# Whitespace_Daughtercard_spi_mux.net
KiCad netlist of a schematic drawn in Altium Designer
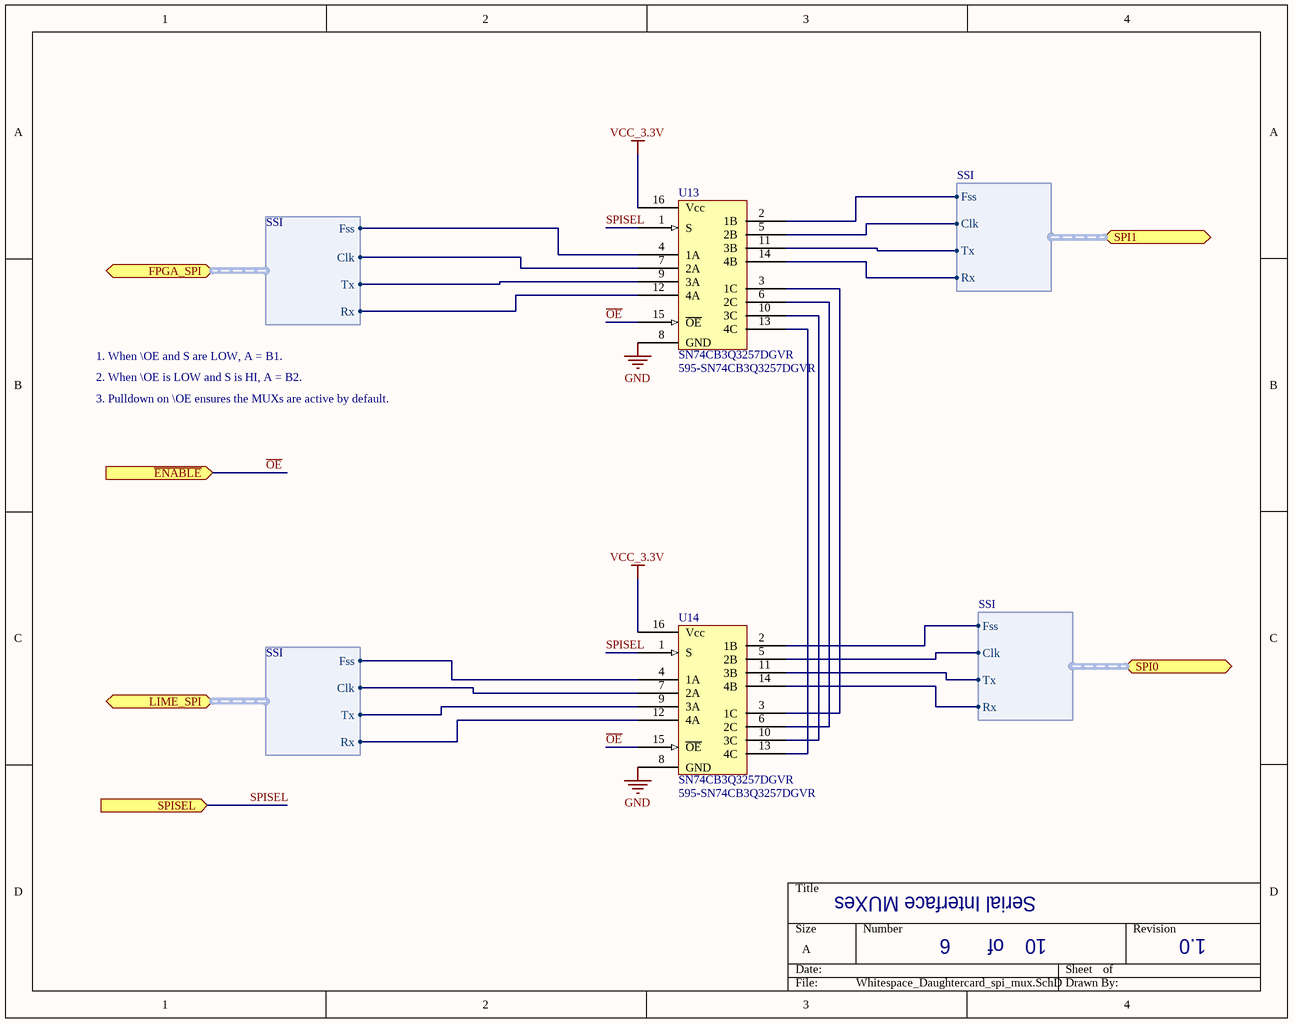
[diagram p0: Whitespace_Daughtercard_spi_mux.SchDoc]

(export (version "E")
  (design (tool "Eeschema 10.0.6"))
  (components
    (comp (ref "U13")
      (value "SN74CB3Q3257DGVR")
      (footprint "TVSOP16_v5")
      (description "4-bit MUX/DEMUX 1-of-2  0-5V SIG 3.3V CTRL TVSOP-16")
      (fields (field (name "SUPPLIER PART NUMBER 1") "595-SN74CB3Q3257DGVR"))
      (libsource (lib "RNG_Parts") (part "SN74CB3Q3257DGVR"))
    )
    (comp (ref "U14")
      (value "SN74CB3Q3257DGVR")
      (footprint "TVSOP16_v5")
      (description "4-bit MUX/DEMUX 1-of-2  0-5V SIG 3.3V CTRL TVSOP-16")
      (fields (field (name "SUPPLIER PART NUMBER 1") "595-SN74CB3Q3257DGVR"))
      (libsource (lib "RNG_Parts") (part "SN74CB3Q3257DGVR"))
    )
  )
  (nets
    (net (code "2") (name "/OE") (class "Default")
      (node (ref "U13") (pin "15") (pinfunction "OE_15") (pintype "input"))
      (node (ref "U14") (pin "15") (pinfunction "OE_15") (pintype "input"))
    )
    (net (code "3") (name "/SPISEL") (class "Default")
      (node (ref "U13") (pin "1") (pinfunction "S_1") (pintype "input"))
      (node (ref "U14") (pin "1") (pinfunction "S_1") (pintype "input"))
    )
    (net (code "5") (name "GND") (class "Default")
      (node (ref "U13") (pin "8") (pinfunction "GND_8") (pintype "power_in"))
      (node (ref "U14") (pin "8") (pinfunction "GND_8") (pintype "power_in"))
    )
    (net (code "6") (name "Net-(U13-1C)") (class "Default")
      (node (ref "U13") (pin "3") (pinfunction "1C_3") (pintype "passive"))
      (node (ref "U14") (pin "3") (pinfunction "1C_3") (pintype "passive"))
    )
    (net (code "7") (name "Net-(U13-2C)") (class "Default")
      (node (ref "U13") (pin "6") (pinfunction "2C_6") (pintype "passive"))
      (node (ref "U14") (pin "6") (pinfunction "2C_6") (pintype "passive"))
    )
    (net (code "8") (name "Net-(U13-3C)") (class "Default")
      (node (ref "U13") (pin "10") (pinfunction "3C_10") (pintype "passive"))
      (node (ref "U14") (pin "10") (pinfunction "3C_10") (pintype "passive"))
    )
    (net (code "9") (name "Net-(U13-4C)") (class "Default")
      (node (ref "U13") (pin "13") (pinfunction "4C_13") (pintype "passive"))
      (node (ref "U14") (pin "13") (pinfunction "4C_13") (pintype "passive"))
    )
    (net (code "10") (name "VCC_3.3V") (class "Default")
      (node (ref "U13") (pin "16") (pinfunction "Vcc_16") (pintype "power_in"))
      (node (ref "U14") (pin "16") (pinfunction "Vcc_16") (pintype "power_in"))
    )
    (net (code "11") (name "unconnected-(U13-1A-Pad4)") (class "Default")
      (node (ref "U13") (pin "4") (pinfunction "1A_4") (pintype "passive"))
    )
    (net (code "12") (name "unconnected-(U13-1B-Pad2)") (class "Default")
      (node (ref "U13") (pin "2") (pinfunction "1B_2") (pintype "passive"))
    )
    (net (code "13") (name "unconnected-(U13-2A-Pad7)") (class "Default")
      (node (ref "U13") (pin "7") (pinfunction "2A_7") (pintype "passive"))
    )
    (net (code "14") (name "unconnected-(U13-2B-Pad5)") (class "Default")
      (node (ref "U13") (pin "5") (pinfunction "2B_5") (pintype "passive"))
    )
    (net (code "15") (name "unconnected-(U13-3A-Pad9)") (class "Default")
      (node (ref "U13") (pin "9") (pinfunction "3A_9") (pintype "passive"))
    )
    (net (code "16") (name "unconnected-(U13-3B-Pad11)") (class "Default")
      (node (ref "U13") (pin "11") (pinfunction "3B_11") (pintype "passive"))
    )
    (net (code "17") (name "unconnected-(U13-4A-Pad12)") (class "Default")
      (node (ref "U13") (pin "12") (pinfunction "4A_12") (pintype "passive"))
    )
    (net (code "18") (name "unconnected-(U13-4B-Pad14)") (class "Default")
      (node (ref "U13") (pin "14") (pinfunction "4B_14") (pintype "passive"))
    )
    (net (code "19") (name "unconnected-(U14-1A-Pad4)") (class "Default")
      (node (ref "U14") (pin "4") (pinfunction "1A_4") (pintype "passive"))
    )
    (net (code "20") (name "unconnected-(U14-1B-Pad2)") (class "Default")
      (node (ref "U14") (pin "2") (pinfunction "1B_2") (pintype "passive"))
    )
    (net (code "21") (name "unconnected-(U14-2A-Pad7)") (class "Default")
      (node (ref "U14") (pin "7") (pinfunction "2A_7") (pintype "passive"))
    )
    (net (code "22") (name "unconnected-(U14-2B-Pad5)") (class "Default")
      (node (ref "U14") (pin "5") (pinfunction "2B_5") (pintype "passive"))
    )
    (net (code "23") (name "unconnected-(U14-3A-Pad9)") (class "Default")
      (node (ref "U14") (pin "9") (pinfunction "3A_9") (pintype "passive"))
    )
    (net (code "24") (name "unconnected-(U14-3B-Pad11)") (class "Default")
      (node (ref "U14") (pin "11") (pinfunction "3B_11") (pintype "passive"))
    )
    (net (code "25") (name "unconnected-(U14-4A-Pad12)") (class "Default")
      (node (ref "U14") (pin "12") (pinfunction "4A_12") (pintype "passive"))
    )
    (net (code "26") (name "unconnected-(U14-4B-Pad14)") (class "Default")
      (node (ref "U14") (pin "14") (pinfunction "4B_14") (pintype "passive"))
    )
  )
)
